# bias-t.net
KiCad netlist of a schematic drawn in EAGLE
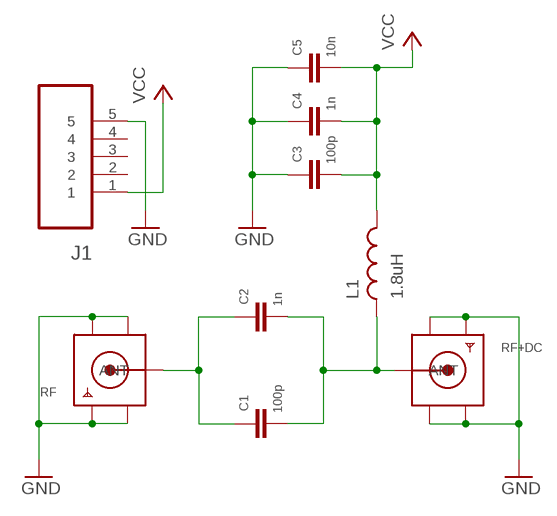
[diagram p0: schematic, sheet 1]

(export (version "E")
  (design (tool "Eeschema 10.0.6"))
  (components
    (comp (ref "C1")
      (value "100p")
      (footprint "eagle-import:0805")
      (libsource (lib "eagle-import") (part "0805CAP"))
    )
    (comp (ref "C2")
      (value "1n")
      (footprint "eagle-import:0805")
      (libsource (lib "eagle-import") (part "0805CAP"))
    )
    (comp (ref "C3")
      (value "100p")
      (footprint "eagle-import:0805")
      (libsource (lib "eagle-import") (part "0805CAP"))
    )
    (comp (ref "C4")
      (value "1n")
      (footprint "eagle-import:0805")
      (libsource (lib "eagle-import") (part "0805CAP"))
    )
    (comp (ref "C5")
      (value "10n")
      (footprint "eagle-import:0805")
      (libsource (lib "eagle-import") (part "0805CAP"))
    )
    (comp (ref "J1")
      (value "47346-0001")
      (footprint "eagle-import:MOLEX_47346-0001")
      (libsource (lib "eagle-import") (part "47346-0001"))
    )
    (comp (ref "L1")
      (value "1.8uH")
      (footprint "eagle-import:1008INDUCTOR")
      (libsource (lib "eagle-import") (part "1008INDUCTOR"))
    )
    (comp (ref "RF")
      (value "SMACONNECTOR_EDGE")
      (footprint "eagle-import:SMA_EDGELAUNCH")
      (libsource (lib "eagle-import") (part "SMACONNECTOR_EDGE"))
    )
    (comp (ref "RF+DC")
      (value "SMACONNECTOR_EDGE")
      (footprint "eagle-import:SMA_EDGELAUNCH")
      (libsource (lib "eagle-import") (part "SMACONNECTOR_EDGE"))
    )
  )
  (nets
    (net (code "1") (name "GND") (class "Default")
      (node (ref "C3") (pin "P$2") (pinfunction "P$2_P$2") (pintype "bidirectional"))
      (node (ref "C4") (pin "P$2") (pinfunction "P$2_P$2") (pintype "bidirectional"))
      (node (ref "C5") (pin "P$2") (pinfunction "P$2_P$2") (pintype "bidirectional"))
      (node (ref "J1") (pin "5") (pinfunction "5_5") (pintype "input"))
      (node (ref "RF") (pin "GND@1") (pinfunction "GND4_GND@1") (pintype "power_in"))
      (node (ref "RF") (pin "GND@2") (pinfunction "GND3_GND@2") (pintype "power_in"))
      (node (ref "RF") (pin "GND@3") (pinfunction "GND2_GND@3") (pintype "power_in"))
      (node (ref "RF") (pin "GND@4") (pinfunction "GND1_GND@4") (pintype "power_in"))
      (node (ref "RF+DC") (pin "GND@1") (pinfunction "GND4_GND@1") (pintype "power_in"))
      (node (ref "RF+DC") (pin "GND@2") (pinfunction "GND3_GND@2") (pintype "power_in"))
      (node (ref "RF+DC") (pin "GND@3") (pinfunction "GND2_GND@3") (pintype "power_in"))
      (node (ref "RF+DC") (pin "GND@4") (pinfunction "GND1_GND@4") (pintype "power_in"))
    )
    (net (code "2") (name "Net-(RF+DC-ANT)") (class "Default")
      (node (ref "C1") (pin "P$1") (pinfunction "P$1_P$1") (pintype "bidirectional"))
      (node (ref "C2") (pin "P$1") (pinfunction "P$1_P$1") (pintype "bidirectional"))
      (node (ref "L1") (pin "P$1") (pinfunction "P$1_P$1") (pintype "bidirectional"))
      (node (ref "RF+DC") (pin "P") (pinfunction "ANT_P") (pintype "bidirectional"))
    )
    (net (code "3") (name "Net-(RF-ANT)") (class "Default")
      (node (ref "C1") (pin "P$2") (pinfunction "P$2_P$2") (pintype "bidirectional"))
      (node (ref "C2") (pin "P$2") (pinfunction "P$2_P$2") (pintype "bidirectional"))
      (node (ref "RF") (pin "P") (pinfunction "ANT_P") (pintype "bidirectional"))
    )
    (net (code "4") (name "VCC") (class "Default")
      (node (ref "C3") (pin "P$1") (pinfunction "P$1_P$1") (pintype "bidirectional"))
      (node (ref "C4") (pin "P$1") (pinfunction "P$1_P$1") (pintype "bidirectional"))
      (node (ref "C5") (pin "P$1") (pinfunction "P$1_P$1") (pintype "bidirectional"))
      (node (ref "J1") (pin "1") (pinfunction "1_1") (pintype "input"))
      (node (ref "L1") (pin "P$2") (pinfunction "P$2_P$2") (pintype "bidirectional"))
    )
    (net (code "5") (name "unconnected-(J1-Pad2)") (class "Default")
      (node (ref "J1") (pin "2") (pinfunction "2_2") (pintype "input"))
    )
    (net (code "6") (name "unconnected-(J1-Pad3)") (class "Default")
      (node (ref "J1") (pin "3") (pinfunction "3_3") (pintype "input"))
    )
    (net (code "7") (name "unconnected-(J1-Pad4)") (class "Default")
      (node (ref "J1") (pin "4") (pinfunction "4_4") (pintype "input"))
    )
  )
)
